# Grove_-_MOSFET.net
KiCad netlist of a schematic drawn in EAGLE
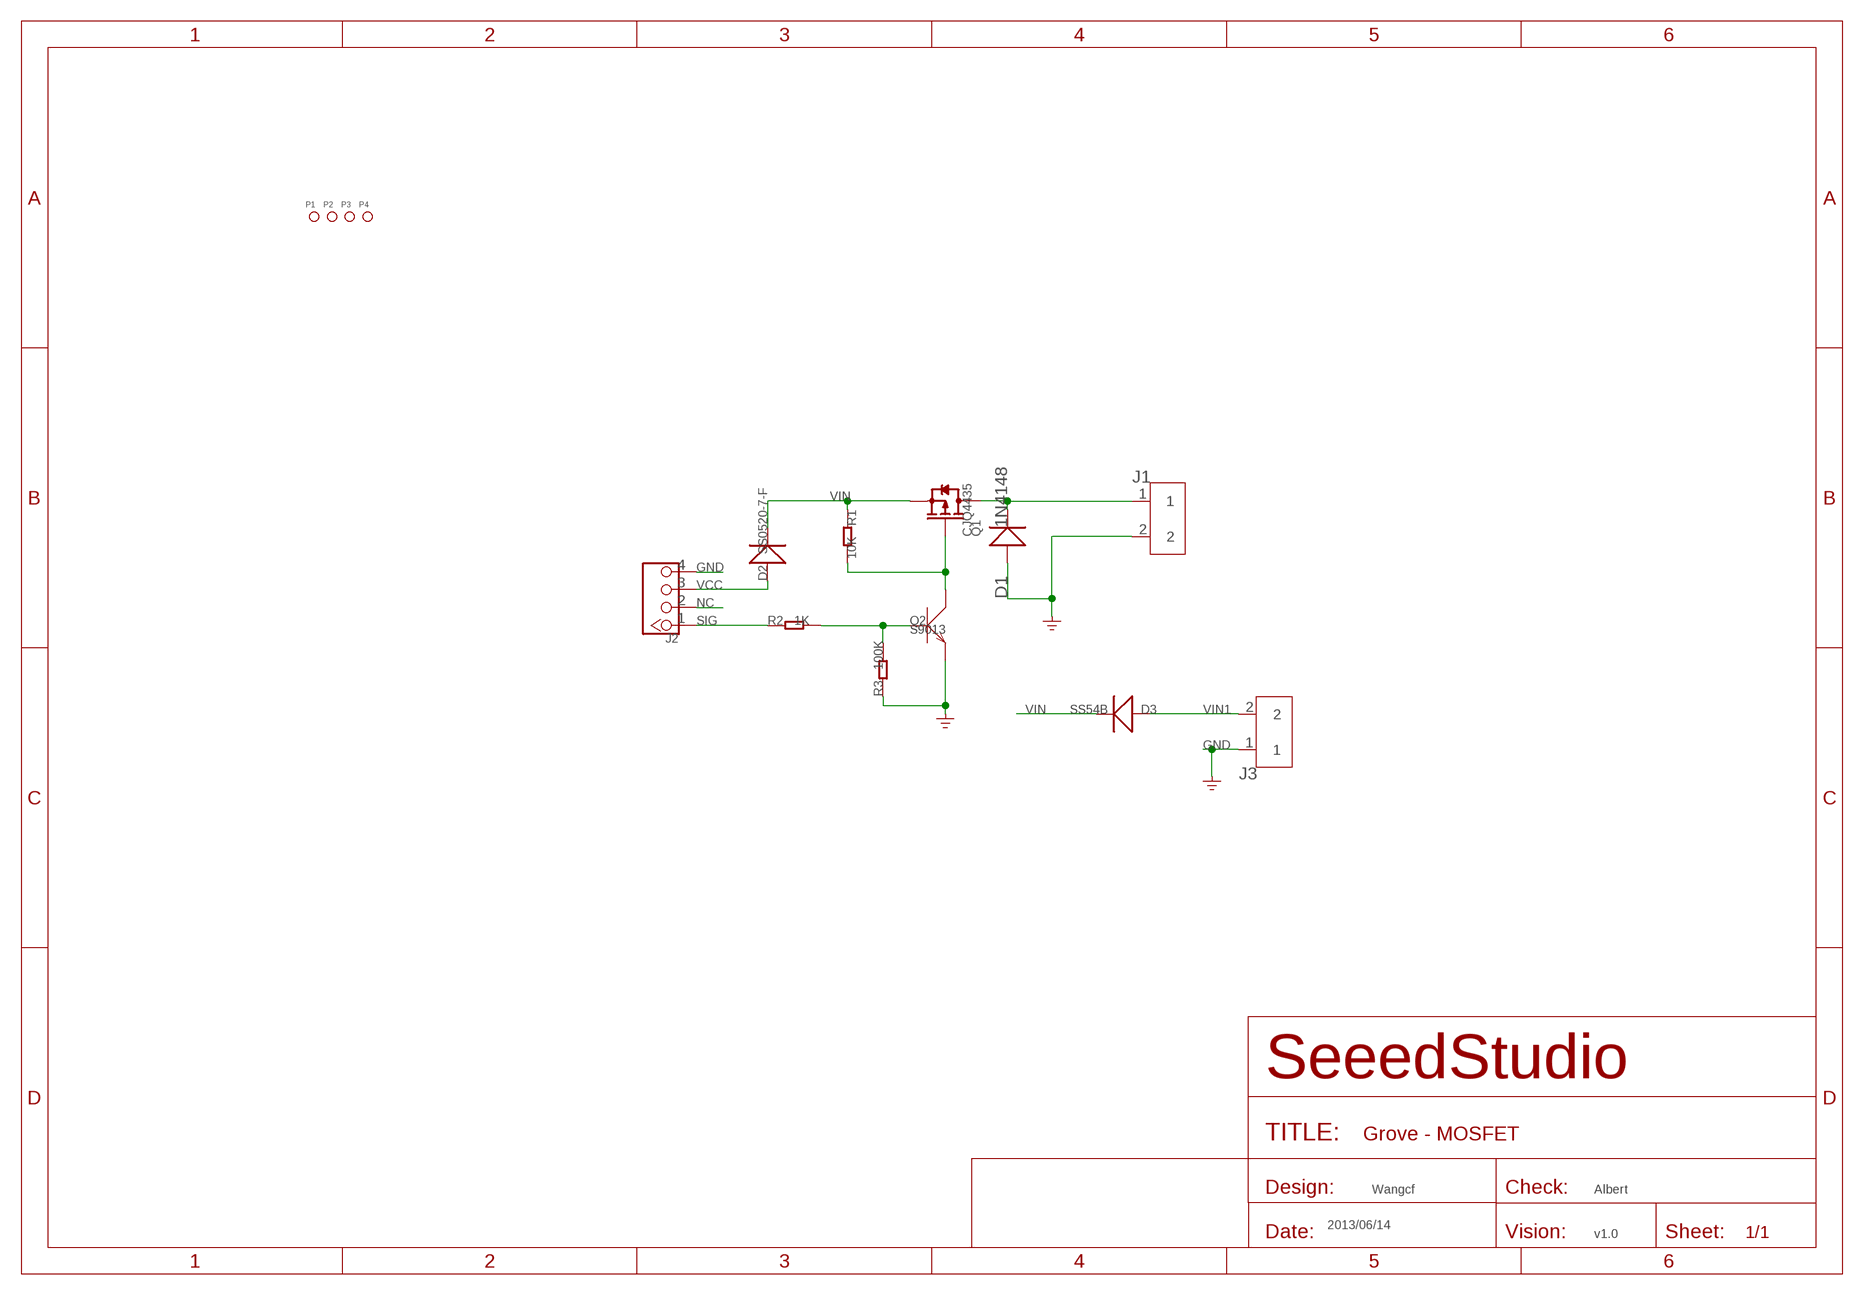
[diagram p0: schematic, sheet 1]

(export (version "E")
  (design (tool "Eeschema 10.0.6"))
  (components
    (comp (ref "D1")
      (value "1N4148")
      (footprint "eagle-import:DO-35-SMD")
      (libsource (lib "eagle-import") (part "D'1N4148-SMD'"))
    )
    (comp (ref "D2")
      (value "SS0520-7-F")
      (footprint "eagle-import:SOD123")
      (libsource (lib "eagle-import") (part "Discrete1_D'1206'"))
    )
    (comp (ref "D3")
      (value "SS54B")
      (footprint "eagle-import:SMB")
      (libsource (lib "eagle-import") (part "D'MBRS240LT3'"))
    )
    (comp (ref "J1")
      (value "SCREW-TERMINAL-2P'5.0-10.6X10X14.8H'")
      (footprint "eagle-import:2P-5.0-10.6X10X14.8H")
      (libsource (lib "eagle-import") (part "SCREW-TERMINAL-2P'5.0-10.6X10X14.8H'"))
    )
    (comp (ref "J2")
      (value "TWIG-4P-2.0-2.0")
      (footprint "eagle-import:4P-2.0")
      (libsource (lib "eagle-import") (part "TWIG-4P-2.0-2.0"))
    )
    (comp (ref "J3")
      (value "SCREW-TERMINAL-2P'5.0-10.6X10X14.8H'")
      (footprint "eagle-import:2P-5.0-10.6X10X14.8H")
      (libsource (lib "eagle-import") (part "SCREW-TERMINAL-2P'5.0-10.6X10X14.8H'"))
    )
    (comp (ref "P1")
      (value "PAD-MARK")
      (footprint "eagle-import:ROUND-MARK-1.0")
      (fields (field (name "PARTNO") "DNP"))
      (libsource (lib "eagle-import") (part "PAD-MARK"))
    )
    (comp (ref "P2")
      (value "PAD-MARK")
      (footprint "eagle-import:ROUND-MARK-1.0")
      (fields (field (name "PARTNO") "DNP"))
      (libsource (lib "eagle-import") (part "PAD-MARK"))
    )
    (comp (ref "P3")
      (value "PAD-MARK")
      (footprint "eagle-import:ROUND-MARK-1.0")
      (fields (field (name "PARTNO") "DNP"))
      (libsource (lib "eagle-import") (part "PAD-MARK"))
    )
    (comp (ref "P4")
      (value "PAD-MARK")
      (footprint "eagle-import:ROUND-MARK-1.0")
      (fields (field (name "PARTNO") "DNP"))
      (libsource (lib "eagle-import") (part "PAD-MARK"))
    )
    (comp (ref "Q1")
      (value "CJQ4435")
      (footprint "eagle-import:SOP8")
      (libsource (lib "eagle-import") (part "MOSFET-P'TPC8127'"))
    )
    (comp (ref "Q2")
      (value "S9013")
      (footprint "eagle-import:SOT23")
      (libsource (lib "eagle-import") (part "TRANSISTOR-NPN-SOT23"))
    )
    (comp (ref "R1")
      (value "10K")
      (footprint "eagle-import:R0603")
      (libsource (lib "eagle-import") (part "R-0603"))
    )
    (comp (ref "R2")
      (value "1K")
      (footprint "eagle-import:R0603")
      (libsource (lib "eagle-import") (part "R-0603"))
    )
    (comp (ref "R3")
      (value "100K")
      (footprint "eagle-import:R0603")
      (libsource (lib "eagle-import") (part "R-0603"))
    )
  )
  (nets
    (net (code "1") (name "/NC") (class "Default")
      (node (ref "J2") (pin "2") (pinfunction "2_2") (pintype "bidirectional"))
    )
    (net (code "2") (name "/SIG") (class "Default")
      (node (ref "J2") (pin "1") (pinfunction "1_1") (pintype "bidirectional"))
      (node (ref "R2") (pin "1") (pinfunction "1_1") (pintype "passive"))
    )
    (net (code "3") (name "/VCC") (class "Default")
      (node (ref "D2") (pin "+") (pinfunction "+_+") (pintype "passive"))
      (node (ref "J2") (pin "3") (pinfunction "3_3") (pintype "bidirectional"))
    )
    (net (code "4") (name "/VIN") (class "Default")
      (node (ref "D2") (pin "-") (pinfunction "-_-") (pintype "passive"))
      (node (ref "D3") (pin "-") (pinfunction "-_-") (pintype "passive"))
      (node (ref "Q1") (pin "1") (pinfunction "S_1") (pintype "passive"))
      (node (ref "Q1") (pin "2") (pinfunction "S_2") (pintype "passive"))
      (node (ref "Q1") (pin "3") (pinfunction "S_3") (pintype "passive"))
      (node (ref "R1") (pin "1") (pinfunction "1_1") (pintype "passive"))
    )
    (net (code "5") (name "/VIN1") (class "Default")
      (node (ref "D3") (pin "+") (pinfunction "+_+") (pintype "passive"))
      (node (ref "J3") (pin "2") (pinfunction "2_2") (pintype "bidirectional"))
    )
    (net (code "6") (name "GND_POWER") (class "Default")
      (node (ref "D1") (pin "A") (pinfunction "+_A") (pintype "passive"))
      (node (ref "J1") (pin "2") (pinfunction "2_2") (pintype "bidirectional"))
      (node (ref "J2") (pin "4") (pinfunction "4_4") (pintype "bidirectional"))
      (node (ref "J3") (pin "1") (pinfunction "1_1") (pintype "bidirectional"))
      (node (ref "Q2") (pin "2") (pinfunction "E_2") (pintype "passive"))
      (node (ref "R3") (pin "1") (pinfunction "1_1") (pintype "passive"))
    )
    (net (code "7") (name "Net-(D1--)") (class "Default")
      (node (ref "D1") (pin "C") (pinfunction "-_C") (pintype "passive"))
      (node (ref "J1") (pin "1") (pinfunction "1_1") (pintype "bidirectional"))
      (node (ref "Q1") (pin "5") (pinfunction "D_5") (pintype "passive"))
      (node (ref "Q1") (pin "6") (pinfunction "D_6") (pintype "passive"))
      (node (ref "Q1") (pin "7") (pinfunction "D_7") (pintype "passive"))
      (node (ref "Q1") (pin "8") (pinfunction "D_8") (pintype "passive"))
    )
    (net (code "8") (name "Net-(Q1-G)") (class "Default")
      (node (ref "Q1") (pin "4") (pinfunction "G_4") (pintype "passive"))
      (node (ref "Q2") (pin "3") (pinfunction "C_3") (pintype "passive"))
      (node (ref "R1") (pin "2") (pinfunction "2_2") (pintype "passive"))
    )
    (net (code "9") (name "Net-(Q2-B)") (class "Default")
      (node (ref "Q2") (pin "1") (pinfunction "B_1") (pintype "passive"))
      (node (ref "R2") (pin "2") (pinfunction "2_2") (pintype "passive"))
      (node (ref "R3") (pin "2") (pinfunction "2_2") (pintype "passive"))
    )
  )
)
